# gate_multiplex.net
KiCad netlist of a schematic drawn in EAGLE
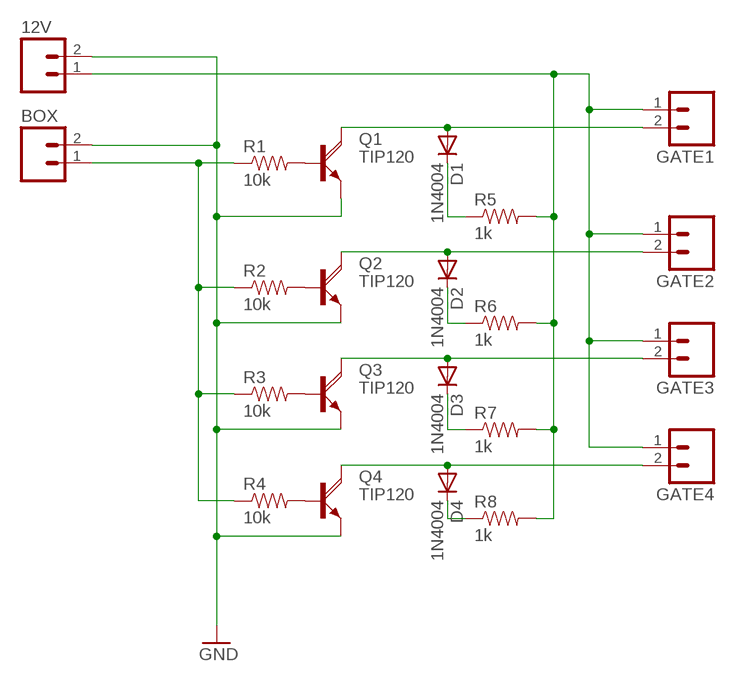
[diagram p0: schematic, sheet 1]

(export (version "E")
  (design (tool "Eeschema 10.0.6"))
  (components
    (comp (ref "12V")
      (value "M02PTH")
      (footprint "eagle-import:1X02")
      (libsource (lib "eagle-import") (part "M02PTH"))
    )
    (comp (ref "BOX")
      (value "M02PTH")
      (footprint "eagle-import:1X02")
      (libsource (lib "eagle-import") (part "M02PTH"))
    )
    (comp (ref "D1")
      (value "1N4004")
      (footprint "eagle-import:DO41-10")
      (libsource (lib "eagle-import") (part "1N4004"))
    )
    (comp (ref "D2")
      (value "1N4004")
      (footprint "eagle-import:DO41-10")
      (libsource (lib "eagle-import") (part "1N4004"))
    )
    (comp (ref "D3")
      (value "1N4004")
      (footprint "eagle-import:DO41-10")
      (libsource (lib "eagle-import") (part "1N4004"))
    )
    (comp (ref "D4")
      (value "1N4004")
      (footprint "eagle-import:DO41-10")
      (libsource (lib "eagle-import") (part "1N4004"))
    )
    (comp (ref "GATE1")
      (value "M02PTH")
      (footprint "eagle-import:1X02")
      (libsource (lib "eagle-import") (part "M02PTH"))
    )
    (comp (ref "GATE2")
      (value "M02PTH")
      (footprint "eagle-import:1X02")
      (libsource (lib "eagle-import") (part "M02PTH"))
    )
    (comp (ref "GATE3")
      (value "M02PTH")
      (footprint "eagle-import:1X02")
      (libsource (lib "eagle-import") (part "M02PTH"))
    )
    (comp (ref "GATE4")
      (value "M02PTH")
      (footprint "eagle-import:1X02")
      (libsource (lib "eagle-import") (part "M02PTH"))
    )
    (comp (ref "Q1")
      (value "TIP120")
      (footprint "eagle-import:TO220V")
      (libsource (lib "eagle-import") (part "TIP120"))
    )
    (comp (ref "Q2")
      (value "TIP120")
      (footprint "eagle-import:TO220V")
      (libsource (lib "eagle-import") (part "TIP120"))
    )
    (comp (ref "Q3")
      (value "TIP120")
      (footprint "eagle-import:TO220V")
      (libsource (lib "eagle-import") (part "TIP120"))
    )
    (comp (ref "Q4")
      (value "TIP120")
      (footprint "eagle-import:TO220V")
      (libsource (lib "eagle-import") (part "TIP120"))
    )
    (comp (ref "R1")
      (value "10k")
      (footprint "eagle-import:1206")
      (libsource (lib "eagle-import") (part "RESISTOR1206"))
    )
    (comp (ref "R2")
      (value "10k")
      (footprint "eagle-import:1206")
      (libsource (lib "eagle-import") (part "RESISTOR1206"))
    )
    (comp (ref "R3")
      (value "10k")
      (footprint "eagle-import:1206")
      (libsource (lib "eagle-import") (part "RESISTOR1206"))
    )
    (comp (ref "R4")
      (value "10k")
      (footprint "eagle-import:1206")
      (libsource (lib "eagle-import") (part "RESISTOR1206"))
    )
    (comp (ref "R5")
      (value "1k")
      (footprint "eagle-import:1206")
      (libsource (lib "eagle-import") (part "RESISTOR1206"))
    )
    (comp (ref "R6")
      (value "1k")
      (footprint "eagle-import:1206")
      (libsource (lib "eagle-import") (part "RESISTOR1206"))
    )
    (comp (ref "R7")
      (value "1k")
      (footprint "eagle-import:1206")
      (libsource (lib "eagle-import") (part "RESISTOR1206"))
    )
    (comp (ref "R8")
      (value "1k")
      (footprint "eagle-import:1206")
      (libsource (lib "eagle-import") (part "RESISTOR1206"))
    )
  )
  (nets
    (net (code "1") (name "GND") (class "Default")
      (node (ref "12V") (pin "2") (pinfunction "2_2") (pintype "passive"))
      (node (ref "BOX") (pin "2") (pinfunction "2_2") (pintype "passive"))
      (node (ref "Q1") (pin "3") (pinfunction "E_3") (pintype "passive"))
      (node (ref "Q2") (pin "3") (pinfunction "E_3") (pintype "passive"))
      (node (ref "Q3") (pin "3") (pinfunction "E_3") (pintype "passive"))
      (node (ref "Q4") (pin "3") (pinfunction "E_3") (pintype "passive"))
    )
    (net (code "2") (name "Net-(12V-Pad1)") (class "Default")
      (node (ref "12V") (pin "1") (pinfunction "1_1") (pintype "passive"))
      (node (ref "GATE1") (pin "1") (pinfunction "1_1") (pintype "passive"))
      (node (ref "GATE2") (pin "1") (pinfunction "1_1") (pintype "passive"))
      (node (ref "GATE3") (pin "1") (pinfunction "1_1") (pintype "passive"))
      (node (ref "GATE4") (pin "1") (pinfunction "1_1") (pintype "passive"))
      (node (ref "R5") (pin "2") (pinfunction "2_2") (pintype "passive"))
      (node (ref "R6") (pin "2") (pinfunction "2_2") (pintype "passive"))
      (node (ref "R7") (pin "2") (pinfunction "2_2") (pintype "passive"))
      (node (ref "R8") (pin "2") (pinfunction "2_2") (pintype "passive"))
    )
    (net (code "3") (name "Net-(BOX-Pad1)") (class "Default")
      (node (ref "BOX") (pin "1") (pinfunction "1_1") (pintype "passive"))
      (node (ref "R1") (pin "1") (pinfunction "1_1") (pintype "passive"))
      (node (ref "R2") (pin "1") (pinfunction "1_1") (pintype "passive"))
      (node (ref "R3") (pin "1") (pinfunction "1_1") (pintype "passive"))
      (node (ref "R4") (pin "1") (pinfunction "1_1") (pintype "passive"))
    )
    (net (code "4") (name "Net-(D1-PadC)") (class "Default")
      (node (ref "D1") (pin "C") (pinfunction "C_C") (pintype "passive"))
      (node (ref "R5") (pin "1") (pinfunction "1_1") (pintype "passive"))
    )
    (net (code "5") (name "Net-(D2-PadC)") (class "Default")
      (node (ref "D2") (pin "C") (pinfunction "C_C") (pintype "passive"))
      (node (ref "R6") (pin "1") (pinfunction "1_1") (pintype "passive"))
    )
    (net (code "6") (name "Net-(D3-PadC)") (class "Default")
      (node (ref "D3") (pin "C") (pinfunction "C_C") (pintype "passive"))
      (node (ref "R7") (pin "1") (pinfunction "1_1") (pintype "passive"))
    )
    (net (code "7") (name "Net-(D4-PadC)") (class "Default")
      (node (ref "D4") (pin "C") (pinfunction "C_C") (pintype "passive"))
      (node (ref "R8") (pin "1") (pinfunction "1_1") (pintype "passive"))
    )
    (net (code "8") (name "Net-(Q1-B)") (class "Default")
      (node (ref "Q1") (pin "1") (pinfunction "B_1") (pintype "passive"))
      (node (ref "R1") (pin "2") (pinfunction "2_2") (pintype "passive"))
    )
    (net (code "9") (name "Net-(Q1-C)") (class "Default")
      (node (ref "D1") (pin "A") (pinfunction "A_A") (pintype "passive"))
      (node (ref "GATE1") (pin "2") (pinfunction "2_2") (pintype "passive"))
      (node (ref "Q1") (pin "2") (pinfunction "C_2") (pintype "passive"))
    )
    (net (code "10") (name "Net-(Q2-B)") (class "Default")
      (node (ref "Q2") (pin "1") (pinfunction "B_1") (pintype "passive"))
      (node (ref "R2") (pin "2") (pinfunction "2_2") (pintype "passive"))
    )
    (net (code "11") (name "Net-(Q2-C)") (class "Default")
      (node (ref "D2") (pin "A") (pinfunction "A_A") (pintype "passive"))
      (node (ref "GATE2") (pin "2") (pinfunction "2_2") (pintype "passive"))
      (node (ref "Q2") (pin "2") (pinfunction "C_2") (pintype "passive"))
    )
    (net (code "12") (name "Net-(Q3-B)") (class "Default")
      (node (ref "Q3") (pin "1") (pinfunction "B_1") (pintype "passive"))
      (node (ref "R3") (pin "2") (pinfunction "2_2") (pintype "passive"))
    )
    (net (code "13") (name "Net-(Q3-C)") (class "Default")
      (node (ref "D3") (pin "A") (pinfunction "A_A") (pintype "passive"))
      (node (ref "GATE3") (pin "2") (pinfunction "2_2") (pintype "passive"))
      (node (ref "Q3") (pin "2") (pinfunction "C_2") (pintype "passive"))
    )
    (net (code "14") (name "Net-(Q4-B)") (class "Default")
      (node (ref "Q4") (pin "1") (pinfunction "B_1") (pintype "passive"))
      (node (ref "R4") (pin "2") (pinfunction "2_2") (pintype "passive"))
    )
    (net (code "15") (name "Net-(Q4-C)") (class "Default")
      (node (ref "D4") (pin "A") (pinfunction "A_A") (pintype "passive"))
      (node (ref "GATE4") (pin "2") (pinfunction "2_2") (pintype "passive"))
      (node (ref "Q4") (pin "2") (pinfunction "C_2") (pintype "passive"))
    )
  )
)
